# FMC_HPC_UFL_DEBUG_HPC_AB.net
KiCad netlist of a schematic drawn in Altium Designer
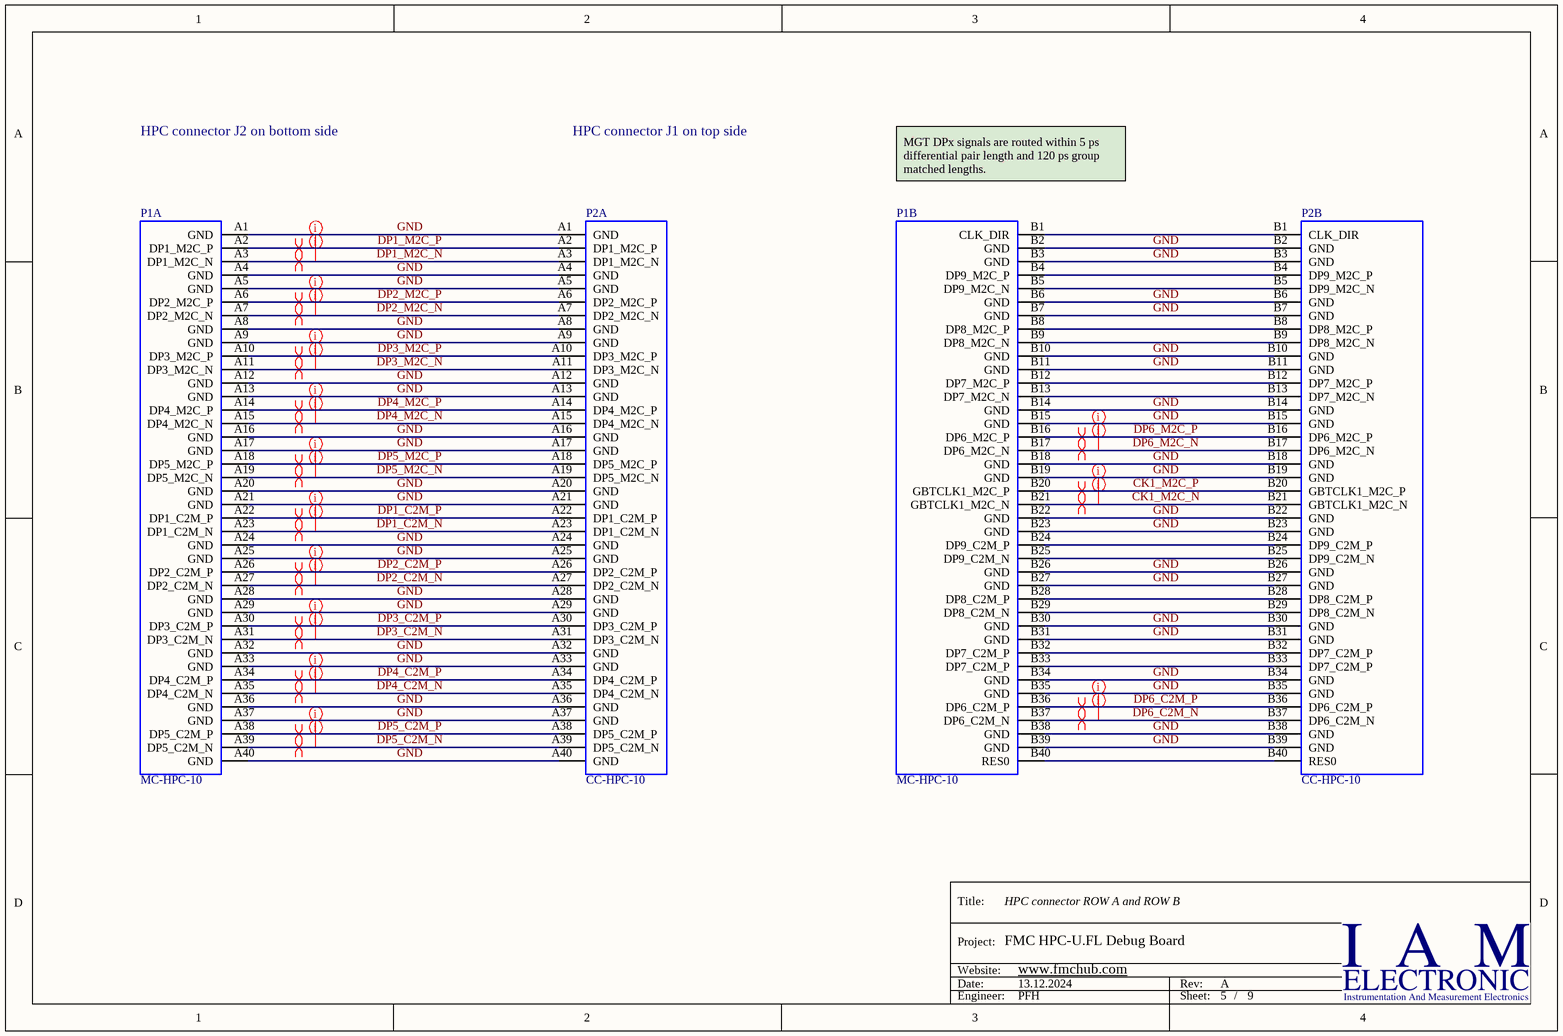
[diagram p0: FMC_HPC_UFL_DEBUG_HPC_AB.SchDoc]

(export (version "E")
  (design (tool "Eeschema 10.0.6"))
  (components
    (comp (ref "P1")
      (value "MC-HPC-10")
      (footprint "ASP-134488-01")
      (description "MC-HPC-10, FMC High-pin count connector, lead free, 400 I/Os, male, 10 mm mated stack height")
      (fields (field (name "MANUFACTURER") "Samtec") (field (name "PART") "ASP-134488-01"))
      (libsource (lib "VITA_57_FMC") (part "MC-HPC-10"))
    )
    (comp (ref "P2")
      (value "CC-HPC-10")
      (footprint "ASP-134486-01")
      (description "CC-HPC-10, FMC High-pin count connector, lead free, 400 I/Os, female, 10 mm mated stack height")
      (fields (field (name "MANUFACTURER") "Samtec") (field (name "PART") "ASP-134486-01"))
      (libsource (lib "VITA_57_FMC") (part "CC-HPC-10"))
    )
  )
  (nets
    (net (code "1") (name "/CK1_M2C_N") (class "Default")
      (node (ref "P1") (pin "B21") (pinfunction "GBTCLK1_M2C_N_B21") (pintype "passive"))
      (node (ref "P2") (pin "B21") (pinfunction "GBTCLK1_M2C_N_B21") (pintype "passive"))
    )
    (net (code "2") (name "/CK1_M2C_P") (class "Default")
      (node (ref "P1") (pin "B20") (pinfunction "GBTCLK1_M2C_P_B20") (pintype "passive"))
      (node (ref "P2") (pin "B20") (pinfunction "GBTCLK1_M2C_P_B20") (pintype "passive"))
    )
    (net (code "3") (name "/DP1_C2M_N") (class "Default")
      (node (ref "P1") (pin "A23") (pinfunction "DP1_C2M_N_A23") (pintype "passive"))
      (node (ref "P2") (pin "A23") (pinfunction "DP1_C2M_N_A23") (pintype "passive"))
    )
    (net (code "4") (name "/DP1_C2M_P") (class "Default")
      (node (ref "P1") (pin "A22") (pinfunction "DP1_C2M_P_A22") (pintype "passive"))
      (node (ref "P2") (pin "A22") (pinfunction "DP1_C2M_P_A22") (pintype "passive"))
    )
    (net (code "5") (name "/DP1_M2C_N") (class "Default")
      (node (ref "P1") (pin "A3") (pinfunction "DP1_M2C_N_A3") (pintype "passive"))
      (node (ref "P2") (pin "A3") (pinfunction "DP1_M2C_N_A3") (pintype "passive"))
    )
    (net (code "6") (name "/DP1_M2C_P") (class "Default")
      (node (ref "P1") (pin "A2") (pinfunction "DP1_M2C_P_A2") (pintype "passive"))
      (node (ref "P2") (pin "A2") (pinfunction "DP1_M2C_P_A2") (pintype "passive"))
    )
    (net (code "7") (name "/DP2_C2M_N") (class "Default")
      (node (ref "P1") (pin "A27") (pinfunction "DP2_C2M_N_A27") (pintype "passive"))
      (node (ref "P2") (pin "A27") (pinfunction "DP2_C2M_N_A27") (pintype "passive"))
    )
    (net (code "8") (name "/DP2_C2M_P") (class "Default")
      (node (ref "P1") (pin "A26") (pinfunction "DP2_C2M_P_A26") (pintype "passive"))
      (node (ref "P2") (pin "A26") (pinfunction "DP2_C2M_P_A26") (pintype "passive"))
    )
    (net (code "9") (name "/DP2_M2C_N") (class "Default")
      (node (ref "P1") (pin "A7") (pinfunction "DP2_M2C_N_A7") (pintype "passive"))
      (node (ref "P2") (pin "A7") (pinfunction "DP2_M2C_N_A7") (pintype "passive"))
    )
    (net (code "10") (name "/DP2_M2C_P") (class "Default")
      (node (ref "P1") (pin "A6") (pinfunction "DP2_M2C_P_A6") (pintype "passive"))
      (node (ref "P2") (pin "A6") (pinfunction "DP2_M2C_P_A6") (pintype "passive"))
    )
    (net (code "11") (name "/DP3_C2M_N") (class "Default")
      (node (ref "P1") (pin "A31") (pinfunction "DP3_C2M_N_A31") (pintype "passive"))
      (node (ref "P2") (pin "A31") (pinfunction "DP3_C2M_N_A31") (pintype "passive"))
    )
    (net (code "12") (name "/DP3_C2M_P") (class "Default")
      (node (ref "P1") (pin "A30") (pinfunction "DP3_C2M_P_A30") (pintype "passive"))
      (node (ref "P2") (pin "A30") (pinfunction "DP3_C2M_P_A30") (pintype "passive"))
    )
    (net (code "13") (name "/DP3_M2C_N") (class "Default")
      (node (ref "P1") (pin "A11") (pinfunction "DP3_M2C_N_A11") (pintype "passive"))
      (node (ref "P2") (pin "A11") (pinfunction "DP3_M2C_N_A11") (pintype "passive"))
    )
    (net (code "14") (name "/DP3_M2C_P") (class "Default")
      (node (ref "P1") (pin "A10") (pinfunction "DP3_M2C_P_A10") (pintype "passive"))
      (node (ref "P2") (pin "A10") (pinfunction "DP3_M2C_P_A10") (pintype "passive"))
    )
    (net (code "15") (name "/DP4_C2M_N") (class "Default")
      (node (ref "P1") (pin "A35") (pinfunction "DP4_C2M_N_A35") (pintype "passive"))
      (node (ref "P2") (pin "A35") (pinfunction "DP4_C2M_N_A35") (pintype "passive"))
    )
    (net (code "16") (name "/DP4_C2M_P") (class "Default")
      (node (ref "P1") (pin "A34") (pinfunction "DP4_C2M_P_A34") (pintype "passive"))
      (node (ref "P2") (pin "A34") (pinfunction "DP4_C2M_P_A34") (pintype "passive"))
    )
    (net (code "17") (name "/DP4_M2C_N") (class "Default")
      (node (ref "P1") (pin "A15") (pinfunction "DP4_M2C_N_A15") (pintype "passive"))
      (node (ref "P2") (pin "A15") (pinfunction "DP4_M2C_N_A15") (pintype "passive"))
    )
    (net (code "18") (name "/DP4_M2C_P") (class "Default")
      (node (ref "P1") (pin "A14") (pinfunction "DP4_M2C_P_A14") (pintype "passive"))
      (node (ref "P2") (pin "A14") (pinfunction "DP4_M2C_P_A14") (pintype "passive"))
    )
    (net (code "19") (name "/DP5_C2M_N") (class "Default")
      (node (ref "P1") (pin "A39") (pinfunction "DP5_C2M_N_A39") (pintype "passive"))
      (node (ref "P2") (pin "A39") (pinfunction "DP5_C2M_N_A39") (pintype "passive"))
    )
    (net (code "20") (name "/DP5_C2M_P") (class "Default")
      (node (ref "P1") (pin "A38") (pinfunction "DP5_C2M_P_A38") (pintype "passive"))
      (node (ref "P2") (pin "A38") (pinfunction "DP5_C2M_P_A38") (pintype "passive"))
    )
    (net (code "21") (name "/DP5_M2C_N") (class "Default")
      (node (ref "P1") (pin "A19") (pinfunction "DP5_M2C_N_A19") (pintype "passive"))
      (node (ref "P2") (pin "A19") (pinfunction "DP5_M2C_N_A19") (pintype "passive"))
    )
    (net (code "22") (name "/DP5_M2C_P") (class "Default")
      (node (ref "P1") (pin "A18") (pinfunction "DP5_M2C_P_A18") (pintype "passive"))
      (node (ref "P2") (pin "A18") (pinfunction "DP5_M2C_P_A18") (pintype "passive"))
    )
    (net (code "23") (name "/DP6_C2M_N") (class "Default")
      (node (ref "P1") (pin "B37") (pinfunction "DP6_C2M_N_B37") (pintype "passive"))
      (node (ref "P2") (pin "B37") (pinfunction "DP6_C2M_N_B37") (pintype "passive"))
    )
    (net (code "24") (name "/DP6_C2M_P") (class "Default")
      (node (ref "P1") (pin "B36") (pinfunction "DP6_C2M_P_B36") (pintype "passive"))
      (node (ref "P2") (pin "B36") (pinfunction "DP6_C2M_P_B36") (pintype "passive"))
    )
    (net (code "25") (name "/DP6_M2C_N") (class "Default")
      (node (ref "P1") (pin "B17") (pinfunction "DP6_M2C_N_B17") (pintype "passive"))
      (node (ref "P2") (pin "B17") (pinfunction "DP6_M2C_N_B17") (pintype "passive"))
    )
    (net (code "26") (name "/DP6_M2C_P") (class "Default")
      (node (ref "P1") (pin "B16") (pinfunction "DP6_M2C_P_B16") (pintype "passive"))
      (node (ref "P2") (pin "B16") (pinfunction "DP6_M2C_P_B16") (pintype "passive"))
    )
    (net (code "27") (name "/GND") (class "Default")
      (node (ref "P1") (pin "A1") (pinfunction "GND_A1") (pintype "passive"))
      (node (ref "P1") (pin "A12") (pinfunction "GND_A12") (pintype "passive"))
      (node (ref "P1") (pin "A13") (pinfunction "GND_A13") (pintype "passive"))
      (node (ref "P1") (pin "A16") (pinfunction "GND_A16") (pintype "passive"))
      (node (ref "P1") (pin "A17") (pinfunction "GND_A17") (pintype "passive"))
      (node (ref "P1") (pin "A20") (pinfunction "GND_A20") (pintype "passive"))
      (node (ref "P1") (pin "A21") (pinfunction "GND_A21") (pintype "passive"))
      (node (ref "P1") (pin "A24") (pinfunction "GND_A24") (pintype "passive"))
      (node (ref "P1") (pin "A25") (pinfunction "GND_A25") (pintype "passive"))
      (node (ref "P1") (pin "A28") (pinfunction "GND_A28") (pintype "passive"))
      (node (ref "P1") (pin "A29") (pinfunction "GND_A29") (pintype "passive"))
      (node (ref "P1") (pin "A32") (pinfunction "GND_A32") (pintype "passive"))
      (node (ref "P1") (pin "A33") (pinfunction "GND_A33") (pintype "passive"))
      (node (ref "P1") (pin "A36") (pinfunction "GND_A36") (pintype "passive"))
      (node (ref "P1") (pin "A37") (pinfunction "GND_A37") (pintype "passive"))
      (node (ref "P1") (pin "A4") (pinfunction "GND_A4") (pintype "passive"))
      (node (ref "P1") (pin "A40") (pinfunction "GND_A40") (pintype "passive"))
      (node (ref "P1") (pin "A5") (pinfunction "GND_A5") (pintype "passive"))
      (node (ref "P1") (pin "A8") (pinfunction "GND_A8") (pintype "passive"))
      (node (ref "P1") (pin "A9") (pinfunction "GND_A9") (pintype "passive"))
      (node (ref "P1") (pin "B10") (pinfunction "GND_B10") (pintype "passive"))
      (node (ref "P1") (pin "B11") (pinfunction "GND_B11") (pintype "passive"))
      (node (ref "P1") (pin "B14") (pinfunction "GND_B14") (pintype "passive"))
      (node (ref "P1") (pin "B15") (pinfunction "GND_B15") (pintype "passive"))
      (node (ref "P1") (pin "B18") (pinfunction "GND_B18") (pintype "passive"))
      (node (ref "P1") (pin "B19") (pinfunction "GND_B19") (pintype "passive"))
      (node (ref "P1") (pin "B2") (pinfunction "GND_B2") (pintype "passive"))
      (node (ref "P1") (pin "B22") (pinfunction "GND_B22") (pintype "passive"))
      (node (ref "P1") (pin "B23") (pinfunction "GND_B23") (pintype "passive"))
      (node (ref "P1") (pin "B26") (pinfunction "GND_B26") (pintype "passive"))
      (node (ref "P1") (pin "B27") (pinfunction "GND_B27") (pintype "passive"))
      (node (ref "P1") (pin "B3") (pinfunction "GND_B3") (pintype "passive"))
      (node (ref "P1") (pin "B30") (pinfunction "GND_B30") (pintype "passive"))
      (node (ref "P1") (pin "B31") (pinfunction "GND_B31") (pintype "passive"))
      (node (ref "P1") (pin "B34") (pinfunction "GND_B34") (pintype "passive"))
      (node (ref "P1") (pin "B35") (pinfunction "GND_B35") (pintype "passive"))
      (node (ref "P1") (pin "B38") (pinfunction "GND_B38") (pintype "passive"))
      (node (ref "P1") (pin "B39") (pinfunction "GND_B39") (pintype "passive"))
      (node (ref "P1") (pin "B6") (pinfunction "GND_B6") (pintype "passive"))
      (node (ref "P1") (pin "B7") (pinfunction "GND_B7") (pintype "passive"))
      (node (ref "P2") (pin "A1") (pinfunction "GND_A1") (pintype "passive"))
      (node (ref "P2") (pin "A12") (pinfunction "GND_A12") (pintype "passive"))
      (node (ref "P2") (pin "A13") (pinfunction "GND_A13") (pintype "passive"))
      (node (ref "P2") (pin "A16") (pinfunction "GND_A16") (pintype "passive"))
      (node (ref "P2") (pin "A17") (pinfunction "GND_A17") (pintype "passive"))
      (node (ref "P2") (pin "A20") (pinfunction "GND_A20") (pintype "passive"))
      (node (ref "P2") (pin "A21") (pinfunction "GND_A21") (pintype "passive"))
      (node (ref "P2") (pin "A24") (pinfunction "GND_A24") (pintype "passive"))
      (node (ref "P2") (pin "A25") (pinfunction "GND_A25") (pintype "passive"))
      (node (ref "P2") (pin "A28") (pinfunction "GND_A28") (pintype "passive"))
      (node (ref "P2") (pin "A29") (pinfunction "GND_A29") (pintype "passive"))
      (node (ref "P2") (pin "A32") (pinfunction "GND_A32") (pintype "passive"))
      (node (ref "P2") (pin "A33") (pinfunction "GND_A33") (pintype "passive"))
      (node (ref "P2") (pin "A36") (pinfunction "GND_A36") (pintype "passive"))
      (node (ref "P2") (pin "A37") (pinfunction "GND_A37") (pintype "passive"))
      (node (ref "P2") (pin "A4") (pinfunction "GND_A4") (pintype "passive"))
      (node (ref "P2") (pin "A40") (pinfunction "GND_A40") (pintype "passive"))
      (node (ref "P2") (pin "A5") (pinfunction "GND_A5") (pintype "passive"))
      (node (ref "P2") (pin "A8") (pinfunction "GND_A8") (pintype "passive"))
      (node (ref "P2") (pin "A9") (pinfunction "GND_A9") (pintype "passive"))
      (node (ref "P2") (pin "B10") (pinfunction "GND_B10") (pintype "passive"))
      (node (ref "P2") (pin "B11") (pinfunction "GND_B11") (pintype "passive"))
      (node (ref "P2") (pin "B14") (pinfunction "GND_B14") (pintype "passive"))
      (node (ref "P2") (pin "B15") (pinfunction "GND_B15") (pintype "passive"))
      (node (ref "P2") (pin "B18") (pinfunction "GND_B18") (pintype "passive"))
      (node (ref "P2") (pin "B19") (pinfunction "GND_B19") (pintype "passive"))
      (node (ref "P2") (pin "B2") (pinfunction "GND_B2") (pintype "passive"))
      (node (ref "P2") (pin "B22") (pinfunction "GND_B22") (pintype "passive"))
      (node (ref "P2") (pin "B23") (pinfunction "GND_B23") (pintype "passive"))
      (node (ref "P2") (pin "B26") (pinfunction "GND_B26") (pintype "passive"))
      (node (ref "P2") (pin "B27") (pinfunction "GND_B27") (pintype "passive"))
      (node (ref "P2") (pin "B3") (pinfunction "GND_B3") (pintype "passive"))
      (node (ref "P2") (pin "B30") (pinfunction "GND_B30") (pintype "passive"))
      (node (ref "P2") (pin "B31") (pinfunction "GND_B31") (pintype "passive"))
      (node (ref "P2") (pin "B34") (pinfunction "GND_B34") (pintype "passive"))
      (node (ref "P2") (pin "B35") (pinfunction "GND_B35") (pintype "passive"))
      (node (ref "P2") (pin "B38") (pinfunction "GND_B38") (pintype "passive"))
      (node (ref "P2") (pin "B39") (pinfunction "GND_B39") (pintype "passive"))
      (node (ref "P2") (pin "B6") (pinfunction "GND_B6") (pintype "passive"))
      (node (ref "P2") (pin "B7") (pinfunction "GND_B7") (pintype "passive"))
    )
    (net (code "28") (name "Net-(P1B-DP7_C2M_P-PadB32)") (class "Default")
      (node (ref "P1") (pin "B32") (pinfunction "DP7_C2M_P_B32") (pintype "passive"))
      (node (ref "P2") (pin "B32") (pinfunction "DP7_C2M_P_B32") (pintype "passive"))
    )
    (net (code "29") (name "Net-(P1B-DP7_C2M_P-PadB33)") (class "Default")
      (node (ref "P1") (pin "B33") (pinfunction "DP7_C2M_P_B33") (pintype "passive"))
      (node (ref "P2") (pin "B33") (pinfunction "DP7_C2M_P_B33") (pintype "passive"))
    )
    (net (code "30") (name "Net-(P1B-DP7_M2C_N)") (class "Default")
      (node (ref "P1") (pin "B13") (pinfunction "DP7_M2C_N_B13") (pintype "passive"))
      (node (ref "P2") (pin "B13") (pinfunction "DP7_M2C_N_B13") (pintype "passive"))
    )
    (net (code "31") (name "Net-(P1B-DP7_M2C_P)") (class "Default")
      (node (ref "P1") (pin "B12") (pinfunction "DP7_M2C_P_B12") (pintype "passive"))
      (node (ref "P2") (pin "B12") (pinfunction "DP7_M2C_P_B12") (pintype "passive"))
    )
    (net (code "32") (name "Net-(P1B-DP8_C2M_N)") (class "Default")
      (node (ref "P1") (pin "B29") (pinfunction "DP8_C2M_N_B29") (pintype "passive"))
      (node (ref "P2") (pin "B29") (pinfunction "DP8_C2M_N_B29") (pintype "passive"))
    )
    (net (code "33") (name "Net-(P1B-DP8_C2M_P)") (class "Default")
      (node (ref "P1") (pin "B28") (pinfunction "DP8_C2M_P_B28") (pintype "passive"))
      (node (ref "P2") (pin "B28") (pinfunction "DP8_C2M_P_B28") (pintype "passive"))
    )
    (net (code "34") (name "Net-(P1B-DP8_M2C_N)") (class "Default")
      (node (ref "P1") (pin "B9") (pinfunction "DP8_M2C_N_B9") (pintype "passive"))
      (node (ref "P2") (pin "B9") (pinfunction "DP8_M2C_N_B9") (pintype "passive"))
    )
    (net (code "35") (name "Net-(P1B-DP8_M2C_P)") (class "Default")
      (node (ref "P1") (pin "B8") (pinfunction "DP8_M2C_P_B8") (pintype "passive"))
      (node (ref "P2") (pin "B8") (pinfunction "DP8_M2C_P_B8") (pintype "passive"))
    )
    (net (code "36") (name "Net-(P1B-DP9_C2M_N)") (class "Default")
      (node (ref "P1") (pin "B25") (pinfunction "DP9_C2M_N_B25") (pintype "passive"))
      (node (ref "P2") (pin "B25") (pinfunction "DP9_C2M_N_B25") (pintype "passive"))
    )
    (net (code "37") (name "Net-(P1B-DP9_C2M_P)") (class "Default")
      (node (ref "P1") (pin "B24") (pinfunction "DP9_C2M_P_B24") (pintype "passive"))
      (node (ref "P2") (pin "B24") (pinfunction "DP9_C2M_P_B24") (pintype "passive"))
    )
    (net (code "38") (name "Net-(P1B-DP9_M2C_N)") (class "Default")
      (node (ref "P1") (pin "B5") (pinfunction "DP9_M2C_N_B5") (pintype "passive"))
      (node (ref "P2") (pin "B5") (pinfunction "DP9_M2C_N_B5") (pintype "passive"))
    )
    (net (code "39") (name "Net-(P1B-DP9_M2C_P)") (class "Default")
      (node (ref "P1") (pin "B4") (pinfunction "DP9_M2C_P_B4") (pintype "passive"))
      (node (ref "P2") (pin "B4") (pinfunction "DP9_M2C_P_B4") (pintype "passive"))
    )
    (net (code "40") (name "Net-(P1B-RES0)") (class "Default")
      (node (ref "P1") (pin "B40") (pinfunction "RES0_B40") (pintype "passive"))
      (node (ref "P2") (pin "B40") (pinfunction "RES0_B40") (pintype "passive"))
    )
    (net (code "41") (name "Net-(P1B-RES1)") (class "Default")
      (node (ref "P1") (pin "B1") (pinfunction "RES1_B1") (pintype "passive"))
      (node (ref "P2") (pin "B1") (pinfunction "RES1_B1") (pintype "passive"))
    )
  )
)
